# PI2_Circuit.net
KiCad netlist of a schematic drawn in Altium Designer
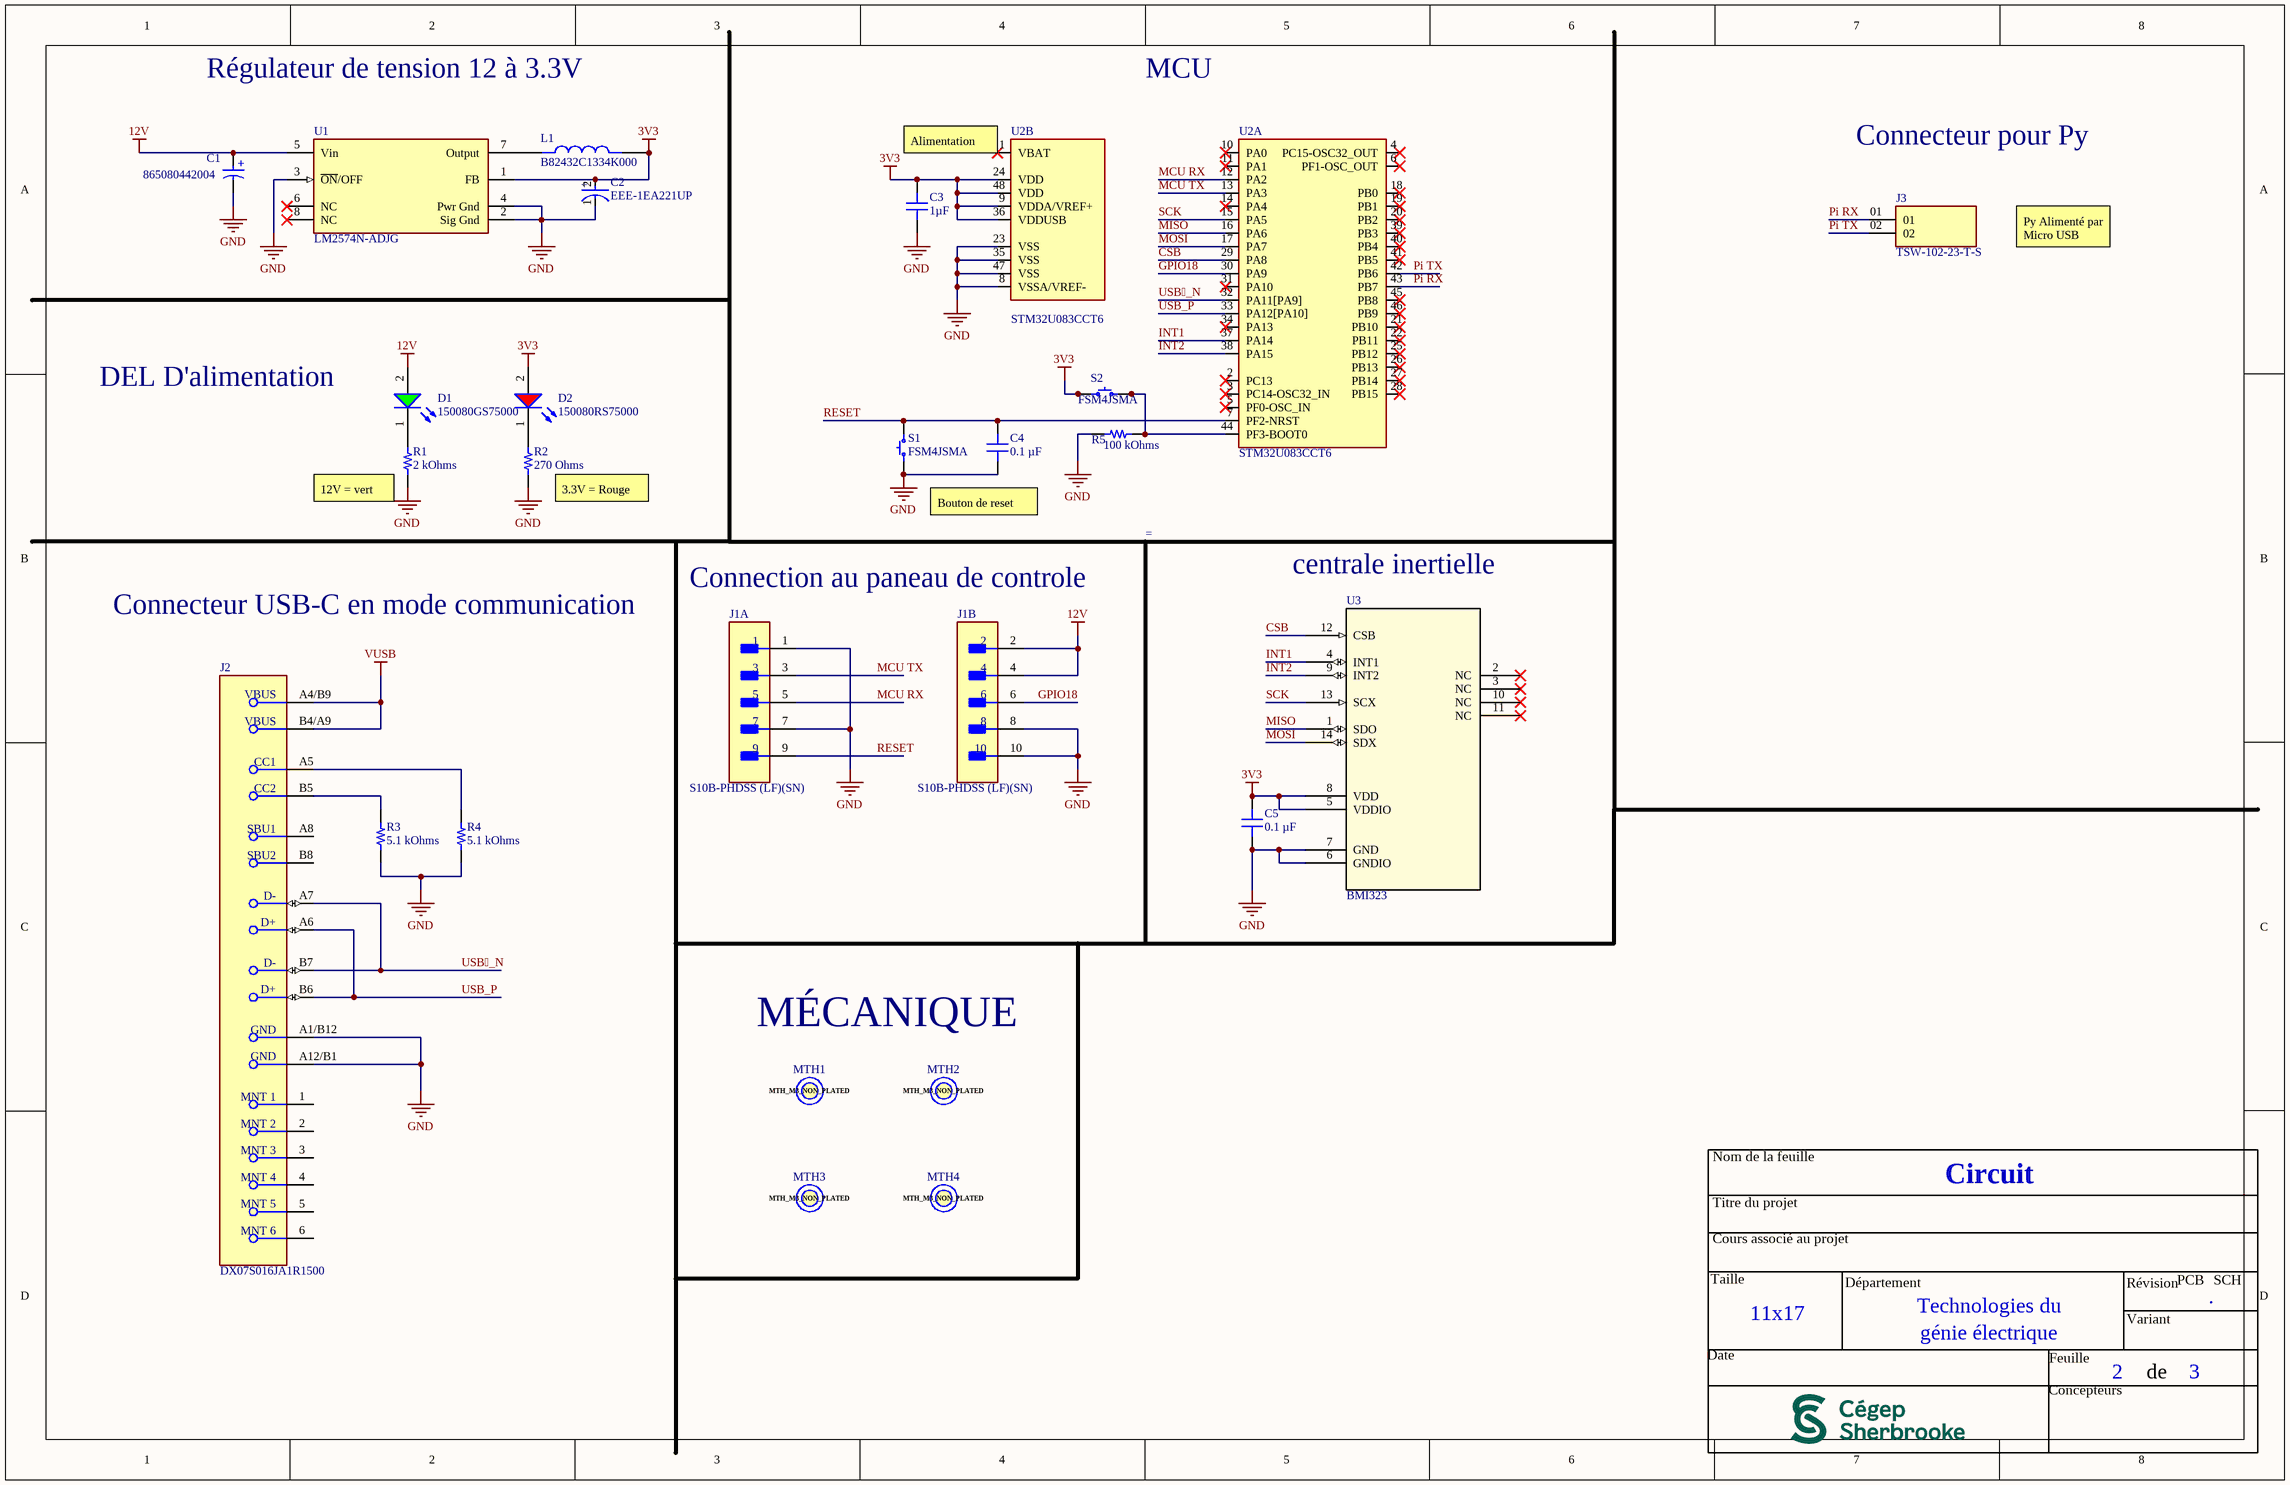
[diagram p0: PI2_Circuit.SchDoc]

(export (version "E")
  (design (tool "Eeschema 10.0.6"))
  (components
    (comp (ref "C1")
      (value "865080442004")
      (footprint "WCAP-ASLI_D5H5.5")
      (description "WCAP-ASLI Aluminum Electrolytic Capacitors")
      (fields (field (name "TOLERANCE") "20%"))
      (libsource (lib "Altium Content Vault") (part "Capacitor_Polarized"))
    )
    (comp (ref "C2")
      (value "EEE-1EA221UP")
      (footprint "FP-SF-MFG")
      (description "CAP ALUM 220UF 20% 25V SMD")
      (fields (field (name "VOLTAGE") "25V") (field (name "TOLERANCE") "20%"))
      (libsource (lib "Altium Content Vault") (part "203bc49f2ac43e59fd269a8c329ed05"))
    )
    (comp (ref "C3")
      (value "1µF")
      (footprint "CAP 0805_2012")
      (description "CAP CER 1UF 10V X7R 0805")
      (fields
        (field (name "PART NUMBER") "MM05ZC105KCZ2A")
        (field (name "CAPACITANCE") "1µF")
        (field (name "MANUFACTURER") "AVX Corporation")
      )
      (libsource (lib "Celestial Altium Library - altium_library") (part "Capacitor"))
    )
    (comp (ref "C4")
      (value "0.1 µF")
      (footprint "CAP 0603_1608")
      (description "CAP CER 0.1UF 50V X7R 0603")
      (fields
        (field (name "PART NUMBER") "C0603C104K5RAC7411")
        (field (name "CAPACITANCE") "0.1 µF")
        (field (name "MANUFACTURER") "KEMET")
      )
      (libsource (lib "Celestial Altium Library - altium_library") (part "Capacitor"))
    )
    (comp (ref "C5")
      (value "0.1 µF")
      (footprint "CAP 0603_1608")
      (description "CAP CER 0.1UF 50V X7R 0603")
      (fields
        (field (name "PART NUMBER") "C0603C104K5RAC7411")
        (field (name "CAPACITANCE") "0.1 µF")
        (field (name "MANUFACTURER") "KEMET")
      )
      (libsource (lib "Celestial Altium Library - altium_library") (part "Capacitor"))
    )
    (comp (ref "D1")
      (value "150080GS75000")
      (footprint "WL-SMCW_0805_150080xx75000")
      (description "WURTH ELEKTRONIK - 150080GS75000 - LED, Green, SMD, 0805, 30 mA, 3.2 V, 520 nm")
      (libsource (lib "Altium Content Vault") (part "LED_Green_2A-1K"))
    )
    (comp (ref "D2")
      (value "150080RS75000")
      (footprint "WL-SMCW_0805_150080xx75000")
      (description "LED Uni-Color Red 630nm 2-Pin Chip 0805(2012Metric) T/R")
      (libsource (lib "Altium Content Vault") (part "LED_Red_2A-1K"))
    )
    (comp (ref "J1")
      (value "S10B-PHDSS (LF)(SN)")
      (footprint "FP-S10B-PHDSS_LF_SN-MFG")
      (description "CONN HEADER R/A 10POS 2MM")
      (libsource (lib "Altium Content Vault") (part "544f42128f4185dcb88ce1ce9bf1982"))
    )
    (comp (ref "J2")
      (value "DX07S016JA1R1500")
      (footprint "FP-DX07S016JA1R1500-MFG")
      (description "CONN RCP USB2.0 TYP C 24P SMD RA")
      (libsource (lib "Altium Content Vault") (part "7f3e9989102a0f22bff9cb010881d34"))
    )
    (comp (ref "J3")
      (value "TSW-102-23-T-S")
      (footprint "SAMTEC_TSW-102-23-T-S")
      (description "Connector Header Through Hole 2 position 0.100 (2.54mm)")
      (fields (field (name "MF") "Samtec"))
      (libsource (lib "TSW-102-23-T-S") (part "TSW-102-23-T-S"))
    )
    (comp (ref "L1")
      (value "B82432C1334K000")
      (footprint "INDM4532X340N")
      (fields (field (name "MF") "TDK Electronics"))
      (libsource (lib "B82432C1334K000") (part "B82432C1334K000"))
    )
    (comp (ref "MTH1")
      (value "MTH_M3_NON_PLATED")
      (footprint "MTH_M3_NON_PLATED")
      (description "MTH - MOUNTING HOLE M3 NON-PLATED - M3")
      (fields (field (name "SOURCE") "CEGEP_SHERBROOKE_TGE_LIBRARY.SchLib"))
      (libsource (lib "Cegep de Sherbrooke") (part "MTH_125MIL_NON-PLATED"))
    )
    (comp (ref "MTH2")
      (value "MTH_M3_NON_PLATED")
      (footprint "MTH_M3_NON_PLATED")
      (description "MTH - MOUNTING HOLE M3 NON-PLATED - M3")
      (fields (field (name "SOURCE") "CEGEP_SHERBROOKE_TGE_LIBRARY.SchLib"))
      (libsource (lib "Cegep de Sherbrooke") (part "MTH_125MIL_NON-PLATED"))
    )
    (comp (ref "MTH3")
      (value "MTH_M3_NON_PLATED")
      (footprint "MTH_M3_NON_PLATED")
      (description "MTH - MOUNTING HOLE M3 NON-PLATED - M3")
      (fields (field (name "SOURCE") "CEGEP_SHERBROOKE_TGE_LIBRARY.SchLib"))
      (libsource (lib "Cegep de Sherbrooke") (part "MTH_125MIL_NON-PLATED"))
    )
    (comp (ref "MTH4")
      (value "MTH_M3_NON_PLATED")
      (footprint "MTH_M3_NON_PLATED")
      (description "MTH - MOUNTING HOLE M3 NON-PLATED - M3")
      (fields (field (name "SOURCE") "CEGEP_SHERBROOKE_TGE_LIBRARY.SchLib"))
      (libsource (lib "Cegep de Sherbrooke") (part "MTH_125MIL_NON-PLATED"))
    )
    (comp (ref "R1")
      (value "2 kOhms")
      (footprint "RES 0603_1608")
      (description "RES 2K OHM 1% 1/10W 0603")
      (fields
        (field (name "PART NUMBER") "RMCF0603FT2K00")
        (field (name "MANUFACTURER") "Stackpole Electronics Inc")
      )
      (libsource (lib "Celestial Altium Library - altium_library") (part "Resistor"))
    )
    (comp (ref "R2")
      (value "270 Ohms")
      (footprint "KOA RES RK73 RN73 0603_1608")
      (description "RES 270 OHM 1% 1/8W 0603")
      (fields
        (field (name "PART NUMBER") "RK73H1JTTD2700F")
        (field (name "MANUFACTURER") "KOA Speer Electronics, Inc.")
      )
      (libsource (lib "Celestial Altium Library - altium_library") (part "Resistor"))
    )
    (comp (ref "R3")
      (value "5.1 kOhms")
      (footprint "YAGEO RES 0603_1608")
      (description "RES SMD 5.1K OHM 1% 1/10W 0603")
      (fields (field (name "PART NUMBER") "AC0603FR-075K1L") (field (name "MANUFACTURER") "Yageo"))
      (libsource (lib "Celestial Altium Library - altium_library") (part "Resistor"))
    )
    (comp (ref "R4")
      (value "5.1 kOhms")
      (footprint "YAGEO RES 0603_1608")
      (description "RES SMD 5.1K OHM 1% 1/10W 0603")
      (fields (field (name "PART NUMBER") "AC0603FR-075K1L") (field (name "MANUFACTURER") "Yageo"))
      (libsource (lib "Celestial Altium Library - altium_library") (part "Resistor"))
    )
    (comp (ref "R5")
      (value "100 kOhms")
      (footprint "RES 0603_1608")
      (description "RES SMD 100K OHM 1% 1/4W 0603")
      (fields (field (name "PART NUMBER") "RCS0603100KFKEA"))
      (libsource (lib "Celestial Altium Library - altium_library") (part "Resistor"))
    )
    (comp (ref "S1")
      (value "FSM4JSMA")
      (footprint "TE FSM4JSMA")
      (description "SWITCH TACTILE SPST-NO 0.05A 24V")
      (fields (field (name "MANUFACTURER") "TE Connectivity ALCOSWITCH Switches"))
      (libsource (lib "Celestial Altium Library - altium_library") (part "SPST-NO 4 PIN"))
    )
    (comp (ref "S2")
      (value "FSM4JSMA")
      (footprint "TE FSM4JSMA")
      (description "SWITCH TACTILE SPST-NO 0.05A 24V")
      (fields (field (name "MANUFACTURER") "TE Connectivity ALCOSWITCH Switches"))
      (libsource (lib "Celestial Altium Library - altium_library") (part "SPST-NO 4 PIN"))
    )
    (comp (ref "U1")
      (value "LM2574N-ADJG")
      (footprint "FP-626-05-MFG")
      (description "LM2574N-ADJG Buck Regulator, Switching, Adjustable Output Voltage, 0.5 A Adjustable 1.23 V to 37 V")
      (libsource (lib "Altium Content Vault") (part "861567207b7aeb512c5a43ca4c5525c"))
    )
    (comp (ref "U2")
      (value "STM32U083CCT6")
      (footprint "STM32U083CCT6-Footprint-1")
      (description "MCU 32-bit ARM Cortex M0+ RISC 256KB Flash 2.5V/3.3V 48-Pin LQFP Tray")
      (libsource (lib "Cegep de Sherbrooke") (part "STM32U083CCT6-Symbol-1"))
    )
    (comp (ref "U3")
      (value "BMI323")
      (footprint "BMI323_BOS")
      (description "Description")
      (fields (field (name "COPYRIGHT") "Copyright (C) 2026 Ultra Librarian. All rights reserved."))
      (libsource (lib "BMI323") (part "BMI323"))
    )
  )
  (nets
    (net (code "1") (name "/CSB") (class "Default")
      (node (ref "U2") (pin "29") (pinfunction "PA8_29") (pintype "passive"))
      (node (ref "U3") (pin "12") (pinfunction "CSB_12") (pintype "input"))
    )
    (net (code "2") (name "/GPIO18") (class "Default")
      (node (ref "J1") (pin "6") (pinfunction "6_6") (pintype "passive"))
      (node (ref "U2") (pin "30") (pinfunction "PA9_30") (pintype "passive"))
    )
    (net (code "3") (name "/INT1") (class "Default")
      (node (ref "U2") (pin "37") (pinfunction "PA14_37") (pintype "passive"))
      (node (ref "U3") (pin "4") (pinfunction "INT1_4") (pintype "bidirectional"))
    )
    (net (code "4") (name "/INT2") (class "Default")
      (node (ref "U2") (pin "38") (pinfunction "PA15_38") (pintype "passive"))
      (node (ref "U3") (pin "9") (pinfunction "INT2_9") (pintype "bidirectional"))
    )
    (net (code "5") (name "/MCU RX") (class "Default")
      (node (ref "J1") (pin "5") (pinfunction "5_5") (pintype "passive"))
      (node (ref "U2") (pin "12") (pinfunction "PA2_12") (pintype "passive"))
    )
    (net (code "6") (name "/MCU TX") (class "Default")
      (node (ref "J1") (pin "3") (pinfunction "3_3") (pintype "passive"))
      (node (ref "U2") (pin "13") (pinfunction "PA3_13") (pintype "passive"))
    )
    (net (code "7") (name "/MISO") (class "Default")
      (node (ref "U2") (pin "16") (pinfunction "PA6_16") (pintype "passive"))
      (node (ref "U3") (pin "1") (pinfunction "SDO_1") (pintype "bidirectional"))
    )
    (net (code "8") (name "/MOSI") (class "Default")
      (node (ref "U2") (pin "17") (pinfunction "PA7_17") (pintype "passive"))
      (node (ref "U3") (pin "14") (pinfunction "SDX_14") (pintype "bidirectional"))
    )
    (net (code "9") (name "/Pi RX") (class "Default")
      (node (ref "J3") (pin "01") (pinfunction "01_01") (pintype "passive"))
      (node (ref "U2") (pin "43") (pinfunction "PB7_43") (pintype "passive"))
    )
    (net (code "10") (name "/Pi TX") (class "Default")
      (node (ref "J3") (pin "02") (pinfunction "02_02") (pintype "passive"))
      (node (ref "U2") (pin "42") (pinfunction "PB6_42") (pintype "passive"))
    )
    (net (code "11") (name "/RESET") (class "Default")
      (node (ref "C4") (pin "2") (pinfunction "2_2") (pintype "passive"))
      (node (ref "J1") (pin "9") (pinfunction "9_9") (pintype "passive"))
      (node (ref "S1") (pin "3") (pinfunction "3_3") (pintype "passive"))
      (node (ref "S1") (pin "4") (pinfunction "4_4") (pintype "passive"))
      (node (ref "U2") (pin "7") (pinfunction "PF2-NRST_7") (pintype "passive"))
    )
    (net (code "12") (name "/SCK") (class "Default")
      (node (ref "U2") (pin "15") (pinfunction "PA5_15") (pintype "passive"))
      (node (ref "U3") (pin "13") (pinfunction "SCX_13") (pintype "input"))
    )
    (net (code "13") (name "/USB_N") (class "Default")
      (node (ref "J2") (pin "A7") (pinfunction "D-_A7") (pintype "bidirectional"))
      (node (ref "J2") (pin "B7") (pinfunction "D-_B7") (pintype "bidirectional"))
      (node (ref "U2") (pin "32") (pinfunction "PA11[PA9]_32") (pintype "passive"))
    )
    (net (code "14") (name "/USB_P") (class "Default")
      (node (ref "J2") (pin "A6") (pinfunction "D+_A6") (pintype "bidirectional"))
      (node (ref "J2") (pin "B6") (pinfunction "D+_B6") (pintype "bidirectional"))
      (node (ref "U2") (pin "33") (pinfunction "PA12[PA10]_33") (pintype "passive"))
    )
    (net (code "15") (name "3V3") (class "Default")
      (node (ref "C2") (pin "2") (pinfunction "A_2") (pintype "passive"))
      (node (ref "C3") (pin "2") (pinfunction "2_2") (pintype "passive"))
      (node (ref "C5") (pin "2") (pinfunction "2_2") (pintype "passive"))
      (node (ref "D2") (pin "2") (pinfunction "A_2") (pintype "passive"))
      (node (ref "L1") (pin "2") (pinfunction "2_2") (pintype "passive"))
      (node (ref "S2") (pin "1") (pinfunction "1_1") (pintype "passive"))
      (node (ref "S2") (pin "2") (pinfunction "2_2") (pintype "passive"))
      (node (ref "U1") (pin "1") (pinfunction "FB_1") (pintype "passive"))
      (node (ref "U2") (pin "24") (pinfunction "VDD_24") (pintype "passive"))
      (node (ref "U2") (pin "36") (pinfunction "VDDUSB_36") (pintype "passive"))
      (node (ref "U2") (pin "48") (pinfunction "VDD_48") (pintype "passive"))
      (node (ref "U2") (pin "9") (pinfunction "VDDA/VREF+_9") (pintype "passive"))
      (node (ref "U3") (pin "5") (pinfunction "VDDIO_5") (pintype "power_in"))
      (node (ref "U3") (pin "8") (pinfunction "VDD_8") (pintype "power_in"))
    )
    (net (code "16") (name "12V") (class "Default")
      (node (ref "C1") (pin "1") (pinfunction "P_1") (pintype "passive"))
      (node (ref "D1") (pin "2") (pinfunction "A_2") (pintype "passive"))
      (node (ref "J1") (pin "2") (pinfunction "2_2") (pintype "passive"))
      (node (ref "J1") (pin "4") (pinfunction "4_4") (pintype "passive"))
      (node (ref "U1") (pin "5") (pinfunction "Vin_5") (pintype "power_in"))
    )
    (net (code "17") (name "GND") (class "Default")
      (node (ref "C1") (pin "2") (pinfunction "N_2") (pintype "passive"))
      (node (ref "C2") (pin "1") (pinfunction "C_1") (pintype "passive"))
      (node (ref "C3") (pin "1") (pinfunction "1_1") (pintype "passive"))
      (node (ref "C4") (pin "1") (pinfunction "1_1") (pintype "passive"))
      (node (ref "C5") (pin "1") (pinfunction "1_1") (pintype "passive"))
      (node (ref "J1") (pin "1") (pinfunction "1_1") (pintype "passive"))
      (node (ref "J1") (pin "10") (pinfunction "10_10") (pintype "passive"))
      (node (ref "J1") (pin "7") (pinfunction "7_7") (pintype "passive"))
      (node (ref "J1") (pin "8") (pinfunction "8_8") (pintype "passive"))
      (node (ref "J2") (pin "A1/B12") (pinfunction "GND_A1/B12") (pintype "power_in"))
      (node (ref "J2") (pin "A12/B1") (pinfunction "GND_A12/B1") (pintype "power_in"))
      (node (ref "R1") (pin "2") (pinfunction "2_2") (pintype "passive"))
      (node (ref "R2") (pin "2") (pinfunction "2_2") (pintype "passive"))
      (node (ref "R3") (pin "1") (pinfunction "1_1") (pintype "passive"))
      (node (ref "R4") (pin "1") (pinfunction "1_1") (pintype "passive"))
      (node (ref "R5") (pin "1") (pinfunction "1_1") (pintype "passive"))
      (node (ref "S1") (pin "1") (pinfunction "1_1") (pintype "passive"))
      (node (ref "S1") (pin "2") (pinfunction "2_2") (pintype "passive"))
      (node (ref "U1") (pin "2") (pinfunction "Sig_Gnd_2") (pintype "power_in"))
      (node (ref "U1") (pin "3") (pinfunction "~{ON}/OFF_3") (pintype "input"))
      (node (ref "U1") (pin "4") (pinfunction "Pwr_Gnd_4") (pintype "power_in"))
      (node (ref "U2") (pin "23") (pinfunction "VSS_23") (pintype "passive"))
      (node (ref "U2") (pin "35") (pinfunction "VSS_35") (pintype "passive"))
      (node (ref "U2") (pin "47") (pinfunction "VSS_47") (pintype "passive"))
      (node (ref "U2") (pin "8") (pinfunction "VSSA/VREF-_8") (pintype "passive"))
      (node (ref "U3") (pin "6") (pinfunction "GNDIO_6") (pintype "power_in"))
      (node (ref "U3") (pin "7") (pinfunction "GND_7") (pintype "power_in"))
    )
    (net (code "18") (name "Net-(D1-K)") (class "Default")
      (node (ref "D1") (pin "1") (pinfunction "K_1") (pintype "passive"))
      (node (ref "R1") (pin "1") (pinfunction "1_1") (pintype "passive"))
    )
    (net (code "19") (name "Net-(D2-K)") (class "Default")
      (node (ref "D2") (pin "1") (pinfunction "K_1") (pintype "passive"))
      (node (ref "R2") (pin "1") (pinfunction "1_1") (pintype "passive"))
    )
    (net (code "20") (name "Net-(J2-CC1)") (class "Default")
      (node (ref "J2") (pin "A5") (pinfunction "CC1_A5") (pintype "passive"))
      (node (ref "R4") (pin "2") (pinfunction "2_2") (pintype "passive"))
    )
    (net (code "21") (name "Net-(J2-CC2)") (class "Default")
      (node (ref "J2") (pin "B5") (pinfunction "CC2_B5") (pintype "passive"))
      (node (ref "R3") (pin "2") (pinfunction "2_2") (pintype "passive"))
    )
    (net (code "22") (name "Net-(U1-Output)") (class "Default")
      (node (ref "L1") (pin "1") (pinfunction "1_1") (pintype "passive"))
      (node (ref "U1") (pin "7") (pinfunction "Output_7") (pintype "passive"))
    )
    (net (code "23") (name "Net-(U2A-PF3-BOOT0)") (class "Default")
      (node (ref "R5") (pin "2") (pinfunction "2_2") (pintype "passive"))
      (node (ref "S2") (pin "3") (pinfunction "3_3") (pintype "passive"))
      (node (ref "S2") (pin "4") (pinfunction "4_4") (pintype "passive"))
      (node (ref "U2") (pin "44") (pinfunction "PF3-BOOT0_44") (pintype "passive"))
    )
    (net (code "24") (name "VUSB") (class "Default")
      (node (ref "J2") (pin "A4/B9") (pinfunction "VBUS_A4/B9") (pintype "power_in"))
      (node (ref "J2") (pin "B4/A9") (pinfunction "VBUS_B4/A9") (pintype "power_in"))
    )
    (net (code "25") (name "unconnected-(J2-MNT_1-Pad1)") (class "Default")
      (node (ref "J2") (pin "1") (pinfunction "MNT_1_1") (pintype "passive"))
    )
    (net (code "26") (name "unconnected-(J2-MNT_2-Pad2)") (class "Default")
      (node (ref "J2") (pin "2") (pinfunction "MNT_2_2") (pintype "passive"))
    )
    (net (code "27") (name "unconnected-(J2-MNT_3-Pad3)") (class "Default")
      (node (ref "J2") (pin "3") (pinfunction "MNT_3_3") (pintype "passive"))
    )
    (net (code "28") (name "unconnected-(J2-MNT_4-Pad4)") (class "Default")
      (node (ref "J2") (pin "4") (pinfunction "MNT_4_4") (pintype "passive"))
    )
    (net (code "29") (name "unconnected-(J2-MNT_5-Pad5)") (class "Default")
      (node (ref "J2") (pin "5") (pinfunction "MNT_5_5") (pintype "passive"))
    )
    (net (code "30") (name "unconnected-(J2-MNT_6-Pad6)") (class "Default")
      (node (ref "J2") (pin "6") (pinfunction "MNT_6_6") (pintype "passive"))
    )
    (net (code "31") (name "unconnected-(J2-SBU1-PadA8)") (class "Default")
      (node (ref "J2") (pin "A8") (pinfunction "SBU1_A8") (pintype "passive"))
    )
    (net (code "32") (name "unconnected-(J2-SBU2-PadB8)") (class "Default")
      (node (ref "J2") (pin "B8") (pinfunction "SBU2_B8") (pintype "passive"))
    )
    (net (code "33") (name "unconnected-(U1-NC-Pad6)") (class "Default")
      (node (ref "U1") (pin "6") (pinfunction "NC_6") (pintype "passive+no_connect"))
    )
    (net (code "34") (name "unconnected-(U1-NC-Pad8)") (class "Default")
      (node (ref "U1") (pin "8") (pinfunction "NC_8") (pintype "passive+no_connect"))
    )
    (net (code "35") (name "unconnected-(U2A-PA0-Pad10)") (class "Default")
      (node (ref "U2") (pin "10") (pinfunction "PA0_10") (pintype "passive+no_connect"))
    )
    (net (code "36") (name "unconnected-(U2A-PA1-Pad11)") (class "Default")
      (node (ref "U2") (pin "11") (pinfunction "PA1_11") (pintype "passive+no_connect"))
    )
    (net (code "37") (name "unconnected-(U2A-PA4-Pad14)") (class "Default")
      (node (ref "U2") (pin "14") (pinfunction "PA4_14") (pintype "passive+no_connect"))
    )
    (net (code "38") (name "unconnected-(U2A-PA10-Pad31)") (class "Default")
      (node (ref "U2") (pin "31") (pinfunction "PA10_31") (pintype "passive+no_connect"))
    )
    (net (code "39") (name "unconnected-(U2A-PA13-Pad34)") (class "Default")
      (node (ref "U2") (pin "34") (pinfunction "PA13_34") (pintype "passive+no_connect"))
    )
    (net (code "40") (name "unconnected-(U2A-PB0-Pad18)") (class "Default")
      (node (ref "U2") (pin "18") (pinfunction "PB0_18") (pintype "passive+no_connect"))
    )
    (net (code "41") (name "unconnected-(U2A-PB1-Pad19)") (class "Default")
      (node (ref "U2") (pin "19") (pinfunction "PB1_19") (pintype "passive+no_connect"))
    )
    (net (code "42") (name "unconnected-(U2A-PB2-Pad20)") (class "Default")
      (node (ref "U2") (pin "20") (pinfunction "PB2_20") (pintype "passive+no_connect"))
    )
    (net (code "43") (name "unconnected-(U2A-PB3-Pad39)") (class "Default")
      (node (ref "U2") (pin "39") (pinfunction "PB3_39") (pintype "passive+no_connect"))
    )
    (net (code "44") (name "unconnected-(U2A-PB4-Pad40)") (class "Default")
      (node (ref "U2") (pin "40") (pinfunction "PB4_40") (pintype "passive+no_connect"))
    )
    (net (code "45") (name "unconnected-(U2A-PB5-Pad41)") (class "Default")
      (node (ref "U2") (pin "41") (pinfunction "PB5_41") (pintype "passive+no_connect"))
    )
    (net (code "46") (name "unconnected-(U2A-PB8-Pad45)") (class "Default")
      (node (ref "U2") (pin "45") (pinfunction "PB8_45") (pintype "passive+no_connect"))
    )
    (net (code "47") (name "unconnected-(U2A-PB9-Pad46)") (class "Default")
      (node (ref "U2") (pin "46") (pinfunction "PB9_46") (pintype "passive+no_connect"))
    )
    (net (code "48") (name "unconnected-(U2A-PB10-Pad21)") (class "Default")
      (node (ref "U2") (pin "21") (pinfunction "PB10_21") (pintype "passive+no_connect"))
    )
    (net (code "49") (name "unconnected-(U2A-PB11-Pad22)") (class "Default")
      (node (ref "U2") (pin "22") (pinfunction "PB11_22") (pintype "passive+no_connect"))
    )
    (net (code "50") (name "unconnected-(U2A-PB12-Pad25)") (class "Default")
      (node (ref "U2") (pin "25") (pinfunction "PB12_25") (pintype "passive+no_connect"))
    )
    (net (code "51") (name "unconnected-(U2A-PB13-Pad26)") (class "Default")
      (node (ref "U2") (pin "26") (pinfunction "PB13_26") (pintype "passive+no_connect"))
    )
    (net (code "52") (name "unconnected-(U2A-PB14-Pad27)") (class "Default")
      (node (ref "U2") (pin "27") (pinfunction "PB14_27") (pintype "passive+no_connect"))
    )
    (net (code "53") (name "unconnected-(U2A-PB15-Pad28)") (class "Default")
      (node (ref "U2") (pin "28") (pinfunction "PB15_28") (pintype "passive+no_connect"))
    )
    (net (code "54") (name "unconnected-(U2A-PC13-Pad2)") (class "Default")
      (node (ref "U2") (pin "2") (pinfunction "PC13_2") (pintype "passive+no_connect"))
    )
    (net (code "55") (name "unconnected-(U2A-PC14-OSC32_IN-Pad3)") (class "Default")
      (node (ref "U2") (pin "3") (pinfunction "PC14-OSC32_IN_3") (pintype "passive+no_connect"))
    )
    (net (code "56") (name "unconnected-(U2A-PC15-OSC32_OUT-Pad4)") (class "Default")
      (node (ref "U2") (pin "4") (pinfunction "PC15-OSC32_OUT_4") (pintype "passive+no_connect"))
    )
    (net (code "57") (name "unconnected-(U2A-PF0-OSC_IN-Pad5)") (class "Default")
      (node (ref "U2") (pin "5") (pinfunction "PF0-OSC_IN_5") (pintype "passive+no_connect"))
    )
    (net (code "58") (name "unconnected-(U2A-PF1-OSC_OUT-Pad6)") (class "Default")
      (node (ref "U2") (pin "6") (pinfunction "PF1-OSC_OUT_6") (pintype "passive+no_connect"))
    )
    (net (code "59") (name "unconnected-(U2B-VBAT-Pad1)") (class "Default")
      (node (ref "U2") (pin "1") (pinfunction "VBAT_1") (pintype "passive+no_connect"))
    )
    (net (code "60") (name "unconnected-(U3-NC-Pad2)") (class "Default")
      (node (ref "U3") (pin "2") (pinfunction "NC_2") (pintype "passive+no_connect"))
    )
    (net (code "61") (name "unconnected-(U3-NC-Pad3)") (class "Default")
      (node (ref "U3") (pin "3") (pinfunction "NC_3") (pintype "passive+no_connect"))
    )
    (net (code "62") (name "unconnected-(U3-NC-Pad10)") (class "Default")
      (node (ref "U3") (pin "10") (pinfunction "NC_10") (pintype "passive+no_connect"))
    )
    (net (code "63") (name "unconnected-(U3-NC-Pad11)") (class "Default")
      (node (ref "U3") (pin "11") (pinfunction "NC_11") (pintype "passive+no_connect"))
    )
  )
)
